# template.net
KiCad netlist of a schematic drawn in EAGLE
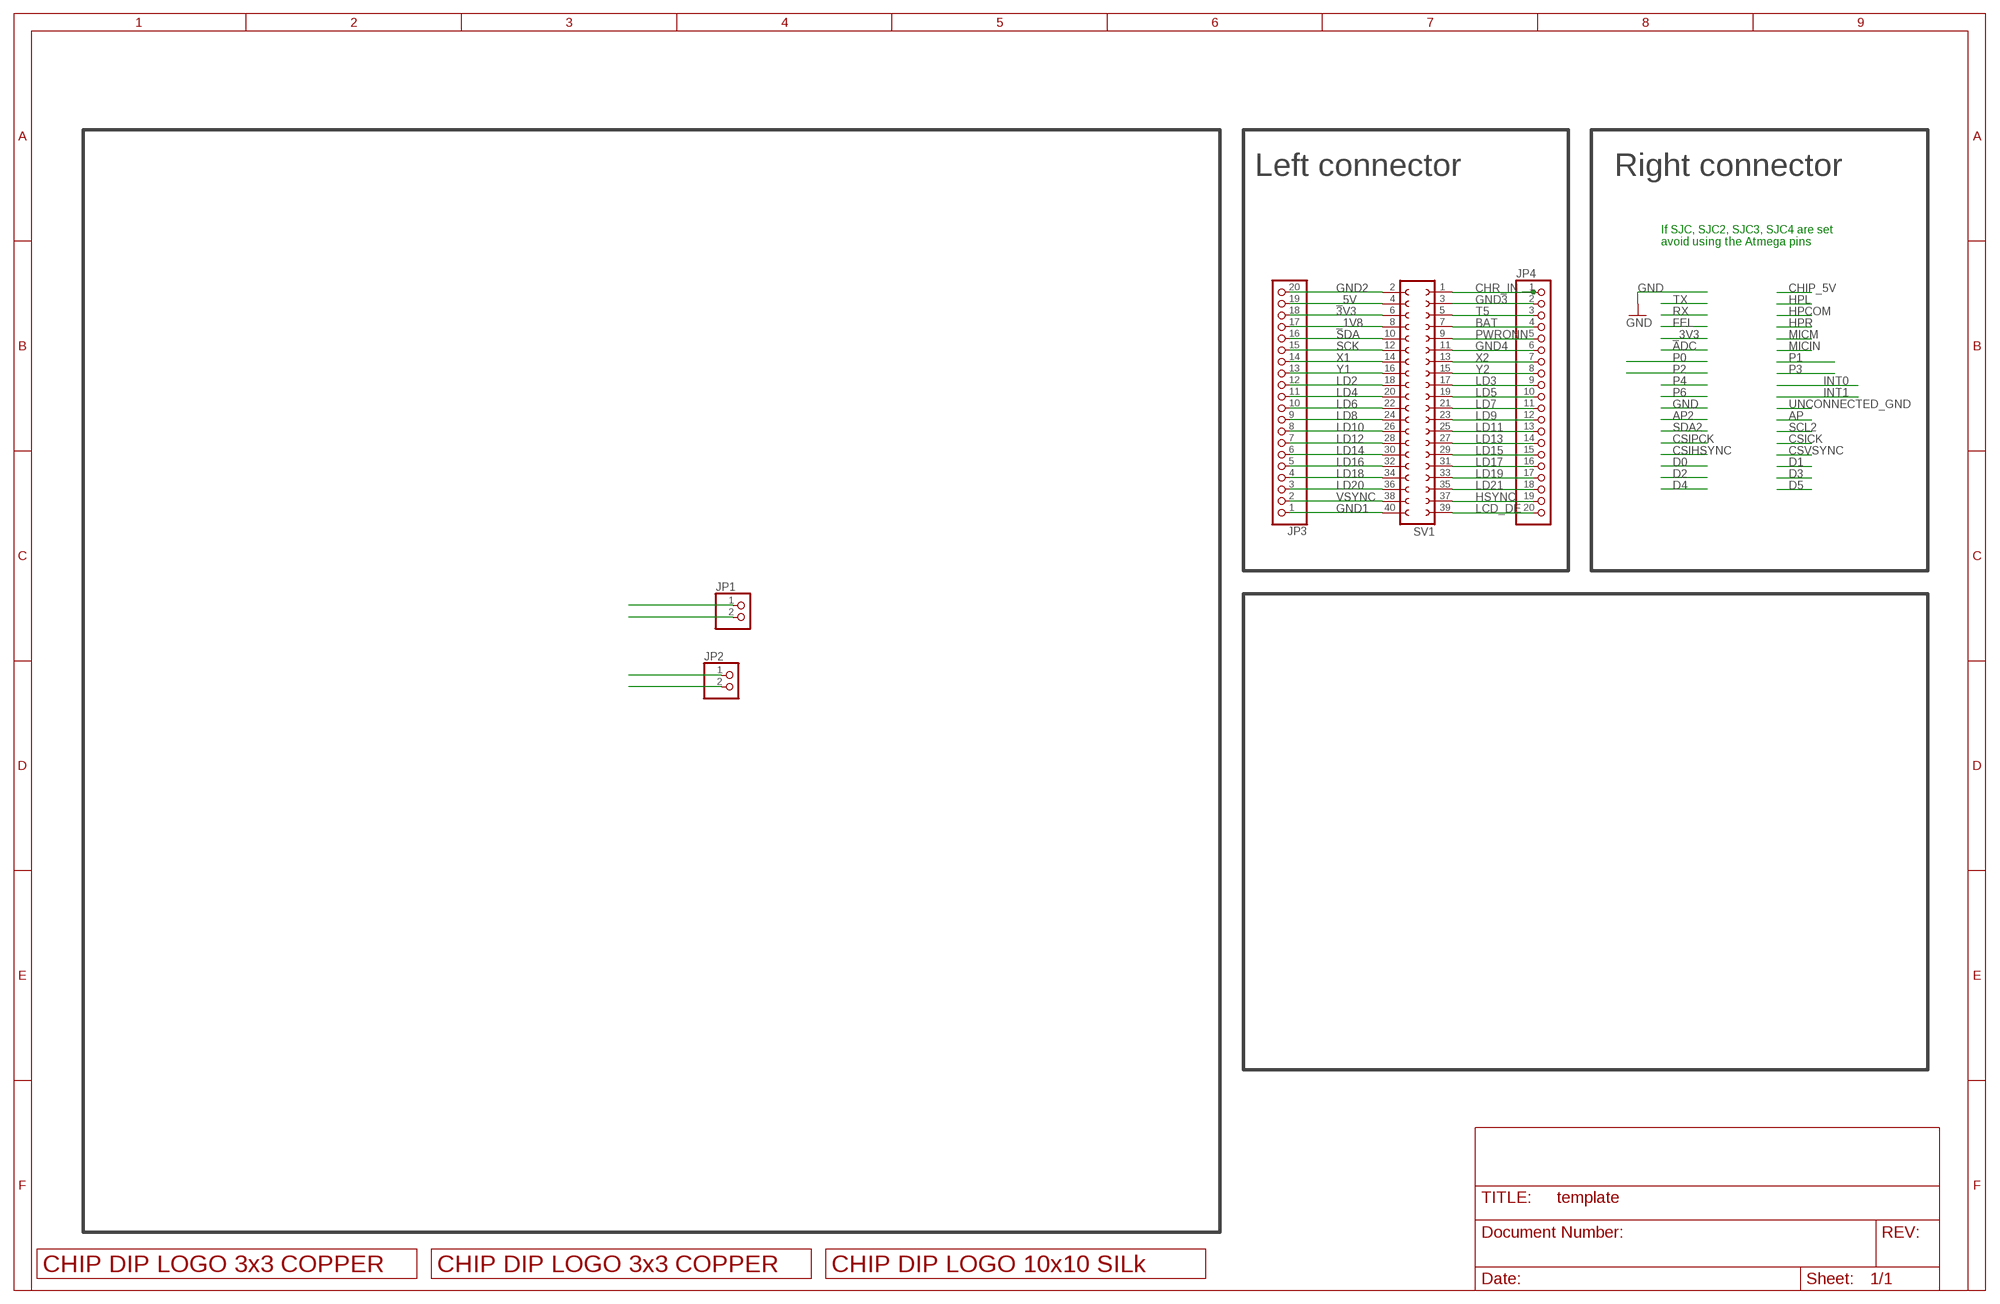
[diagram p0: schematic, sheet 1]

(export (version "E")
  (design (tool "Eeschema 10.0.6"))
  (components
    (comp (ref "JP1")
      (value "PINHD-1X2")
      (footprint "eagle-import:1X02")
      (libsource (lib "eagle-import") (part "PINHD-1X2"))
    )
    (comp (ref "JP2")
      (value "PINHD-1X2")
      (footprint "eagle-import:1X02")
      (libsource (lib "eagle-import") (part "PINHD-1X2"))
    )
    (comp (ref "JP3")
      (value "PINHD-1X20")
      (footprint "eagle-import:1X20")
      (libsource (lib "eagle-import") (part "PINHD-1X20"))
    )
    (comp (ref "JP4")
      (value "PINHD-1X20")
      (footprint "eagle-import:1X20")
      (libsource (lib "eagle-import") (part "PINHD-1X20"))
    )
    (comp (ref "SV1")
      (value "FE20-2")
      (footprint "eagle-import:FE20-2")
      (libsource (lib "eagle-import") (part "FE20-2"))
    )
    (comp (ref "U$2")
      (value "LOGO_3X3_COPPER")
      (footprint "eagle-import:LOGO_3X3_COPPER")
      (libsource (lib "eagle-import") (part "LOGO_3X3_COPPER"))
    )
    (comp (ref "U$4")
      (value "LOGO_3X3_COPPER")
      (footprint "eagle-import:LOGO_3X3_COPPER")
      (libsource (lib "eagle-import") (part "LOGO_3X3_COPPER"))
    )
    (comp (ref "U$5")
      (value "LOGO_10X10_SILK")
      (footprint "eagle-import:LOGO_10X10_SILK")
      (libsource (lib "eagle-import") (part "LOGO_10X10_SILK"))
    )
  )
  (nets
    (net (code "1") (name "/3V3") (class "Default")
      (node (ref "JP2") (pin "2") (pinfunction "2_2") (pintype "passive"))
      (node (ref "JP3") (pin "18") (pinfunction "18_18") (pintype "passive"))
      (node (ref "SV1") (pin "6") (pinfunction "6_6") (pintype "passive"))
    )
    (net (code "5") (name "/BAT") (class "Default")
      (node (ref "JP4") (pin "4") (pinfunction "4_4") (pintype "passive"))
      (node (ref "SV1") (pin "7") (pinfunction "7_7") (pintype "passive"))
    )
    (net (code "7") (name "/CHR_IN") (class "Default")
      (node (ref "JP1") (pin "1") (pinfunction "1_1") (pintype "passive"))
      (node (ref "JP4") (pin "1") (pinfunction "1_1") (pintype "passive"))
      (node (ref "SV1") (pin "1") (pinfunction "1_1") (pintype "passive"))
    )
    (net (code "19") (name "/GND1") (class "Default")
      (node (ref "JP3") (pin "1") (pinfunction "1_1") (pintype "passive"))
      (node (ref "SV1") (pin "40") (pinfunction "40_40") (pintype "passive"))
    )
    (net (code "20") (name "/GND2") (class "Default")
      (node (ref "JP1") (pin "2") (pinfunction "2_2") (pintype "passive"))
      (node (ref "JP3") (pin "20") (pinfunction "20_20") (pintype "passive"))
      (node (ref "SV1") (pin "2") (pinfunction "2_2") (pintype "passive"))
    )
    (net (code "21") (name "/GND3") (class "Default")
      (node (ref "JP2") (pin "1") (pinfunction "1_1") (pintype "passive"))
      (node (ref "JP4") (pin "2") (pinfunction "2_2") (pintype "passive"))
      (node (ref "SV1") (pin "3") (pinfunction "3_3") (pintype "passive"))
    )
    (net (code "22") (name "/GND4") (class "Default")
      (node (ref "JP4") (pin "6") (pinfunction "6_6") (pintype "passive"))
      (node (ref "SV1") (pin "11") (pinfunction "11_11") (pintype "passive"))
    )
    (net (code "26") (name "/HSYNC") (class "Default")
      (node (ref "JP4") (pin "19") (pinfunction "19_19") (pintype "passive"))
      (node (ref "SV1") (pin "37") (pinfunction "37_37") (pintype "passive"))
    )
    (net (code "29") (name "/LCD_DE") (class "Default")
      (node (ref "JP4") (pin "20") (pinfunction "20_20") (pintype "passive"))
      (node (ref "SV1") (pin "39") (pinfunction "39_39") (pintype "passive"))
    )
    (net (code "30") (name "/LD2") (class "Default")
      (node (ref "JP3") (pin "12") (pinfunction "12_12") (pintype "passive"))
      (node (ref "SV1") (pin "18") (pinfunction "18_18") (pintype "passive"))
    )
    (net (code "31") (name "/LD3") (class "Default")
      (node (ref "JP4") (pin "9") (pinfunction "9_9") (pintype "passive"))
      (node (ref "SV1") (pin "17") (pinfunction "17_17") (pintype "passive"))
    )
    (net (code "32") (name "/LD4") (class "Default")
      (node (ref "JP3") (pin "11") (pinfunction "11_11") (pintype "passive"))
      (node (ref "SV1") (pin "20") (pinfunction "20_20") (pintype "passive"))
    )
    (net (code "33") (name "/LD5") (class "Default")
      (node (ref "JP4") (pin "10") (pinfunction "10_10") (pintype "passive"))
      (node (ref "SV1") (pin "19") (pinfunction "19_19") (pintype "passive"))
    )
    (net (code "34") (name "/LD6") (class "Default")
      (node (ref "JP3") (pin "10") (pinfunction "10_10") (pintype "passive"))
      (node (ref "SV1") (pin "22") (pinfunction "22_22") (pintype "passive"))
    )
    (net (code "35") (name "/LD7") (class "Default")
      (node (ref "JP4") (pin "11") (pinfunction "11_11") (pintype "passive"))
      (node (ref "SV1") (pin "21") (pinfunction "21_21") (pintype "passive"))
    )
    (net (code "36") (name "/LD8") (class "Default")
      (node (ref "JP3") (pin "9") (pinfunction "9_9") (pintype "passive"))
      (node (ref "SV1") (pin "24") (pinfunction "24_24") (pintype "passive"))
    )
    (net (code "37") (name "/LD9") (class "Default")
      (node (ref "JP4") (pin "12") (pinfunction "12_12") (pintype "passive"))
      (node (ref "SV1") (pin "23") (pinfunction "23_23") (pintype "passive"))
    )
    (net (code "38") (name "/LD10") (class "Default")
      (node (ref "JP3") (pin "8") (pinfunction "8_8") (pintype "passive"))
      (node (ref "SV1") (pin "26") (pinfunction "26_26") (pintype "passive"))
    )
    (net (code "39") (name "/LD11") (class "Default")
      (node (ref "JP4") (pin "13") (pinfunction "13_13") (pintype "passive"))
      (node (ref "SV1") (pin "25") (pinfunction "25_25") (pintype "passive"))
    )
    (net (code "40") (name "/LD12") (class "Default")
      (node (ref "JP3") (pin "7") (pinfunction "7_7") (pintype "passive"))
      (node (ref "SV1") (pin "28") (pinfunction "28_28") (pintype "passive"))
    )
    (net (code "41") (name "/LD13") (class "Default")
      (node (ref "JP4") (pin "14") (pinfunction "14_14") (pintype "passive"))
      (node (ref "SV1") (pin "27") (pinfunction "27_27") (pintype "passive"))
    )
    (net (code "42") (name "/LD14") (class "Default")
      (node (ref "JP3") (pin "6") (pinfunction "6_6") (pintype "passive"))
      (node (ref "SV1") (pin "30") (pinfunction "30_30") (pintype "passive"))
    )
    (net (code "43") (name "/LD15") (class "Default")
      (node (ref "JP4") (pin "15") (pinfunction "15_15") (pintype "passive"))
      (node (ref "SV1") (pin "29") (pinfunction "29_29") (pintype "passive"))
    )
    (net (code "44") (name "/LD16") (class "Default")
      (node (ref "JP3") (pin "5") (pinfunction "5_5") (pintype "passive"))
      (node (ref "SV1") (pin "32") (pinfunction "32_32") (pintype "passive"))
    )
    (net (code "45") (name "/LD17") (class "Default")
      (node (ref "JP4") (pin "16") (pinfunction "16_16") (pintype "passive"))
      (node (ref "SV1") (pin "31") (pinfunction "31_31") (pintype "passive"))
    )
    (net (code "46") (name "/LD18") (class "Default")
      (node (ref "JP3") (pin "4") (pinfunction "4_4") (pintype "passive"))
      (node (ref "SV1") (pin "34") (pinfunction "34_34") (pintype "passive"))
    )
    (net (code "47") (name "/LD19") (class "Default")
      (node (ref "JP4") (pin "17") (pinfunction "17_17") (pintype "passive"))
      (node (ref "SV1") (pin "33") (pinfunction "33_33") (pintype "passive"))
    )
    (net (code "48") (name "/LD20") (class "Default")
      (node (ref "JP3") (pin "3") (pinfunction "3_3") (pintype "passive"))
      (node (ref "SV1") (pin "36") (pinfunction "36_36") (pintype "passive"))
    )
    (net (code "49") (name "/LD21") (class "Default")
      (node (ref "JP4") (pin "18") (pinfunction "18_18") (pintype "passive"))
      (node (ref "SV1") (pin "35") (pinfunction "35_35") (pintype "passive"))
    )
    (net (code "58") (name "/PWRONN") (class "Default")
      (node (ref "JP4") (pin "5") (pinfunction "5_5") (pintype "passive"))
      (node (ref "SV1") (pin "9") (pinfunction "9_9") (pintype "passive"))
    )
    (net (code "60") (name "/SCK") (class "Default")
      (node (ref "JP3") (pin "15") (pinfunction "15_15") (pintype "passive"))
      (node (ref "SV1") (pin "12") (pinfunction "12_12") (pintype "passive"))
    )
    (net (code "62") (name "/SDA") (class "Default")
      (node (ref "JP3") (pin "16") (pinfunction "16_16") (pintype "passive"))
      (node (ref "SV1") (pin "10") (pinfunction "10_10") (pintype "passive"))
    )
    (net (code "64") (name "/T5") (class "Default")
      (node (ref "JP4") (pin "3") (pinfunction "3_3") (pintype "passive"))
      (node (ref "SV1") (pin "5") (pinfunction "5_5") (pintype "passive"))
    )
    (net (code "67") (name "/VSYNC") (class "Default")
      (node (ref "JP3") (pin "2") (pinfunction "2_2") (pintype "passive"))
      (node (ref "SV1") (pin "38") (pinfunction "38_38") (pintype "passive"))
    )
    (net (code "68") (name "/X1") (class "Default")
      (node (ref "JP3") (pin "14") (pinfunction "14_14") (pintype "passive"))
      (node (ref "SV1") (pin "14") (pinfunction "14_14") (pintype "passive"))
    )
    (net (code "69") (name "/X2") (class "Default")
      (node (ref "JP4") (pin "7") (pinfunction "7_7") (pintype "passive"))
      (node (ref "SV1") (pin "13") (pinfunction "13_13") (pintype "passive"))
    )
    (net (code "70") (name "/Y1") (class "Default")
      (node (ref "JP3") (pin "13") (pinfunction "13_13") (pintype "passive"))
      (node (ref "SV1") (pin "16") (pinfunction "16_16") (pintype "passive"))
    )
    (net (code "71") (name "/Y2") (class "Default")
      (node (ref "JP4") (pin "8") (pinfunction "8_8") (pintype "passive"))
      (node (ref "SV1") (pin "15") (pinfunction "15_15") (pintype "passive"))
    )
    (net (code "72") (name "/_1V8") (class "Default")
      (node (ref "JP3") (pin "17") (pinfunction "17_17") (pintype "passive"))
      (node (ref "SV1") (pin "8") (pinfunction "8_8") (pintype "passive"))
    )
    (net (code "74") (name "/_5V") (class "Default")
      (node (ref "JP3") (pin "19") (pinfunction "19_19") (pintype "passive"))
      (node (ref "SV1") (pin "4") (pinfunction "4_4") (pintype "passive"))
    )
  )
)
